# Main.net
KiCad netlist of a schematic drawn in EAGLE
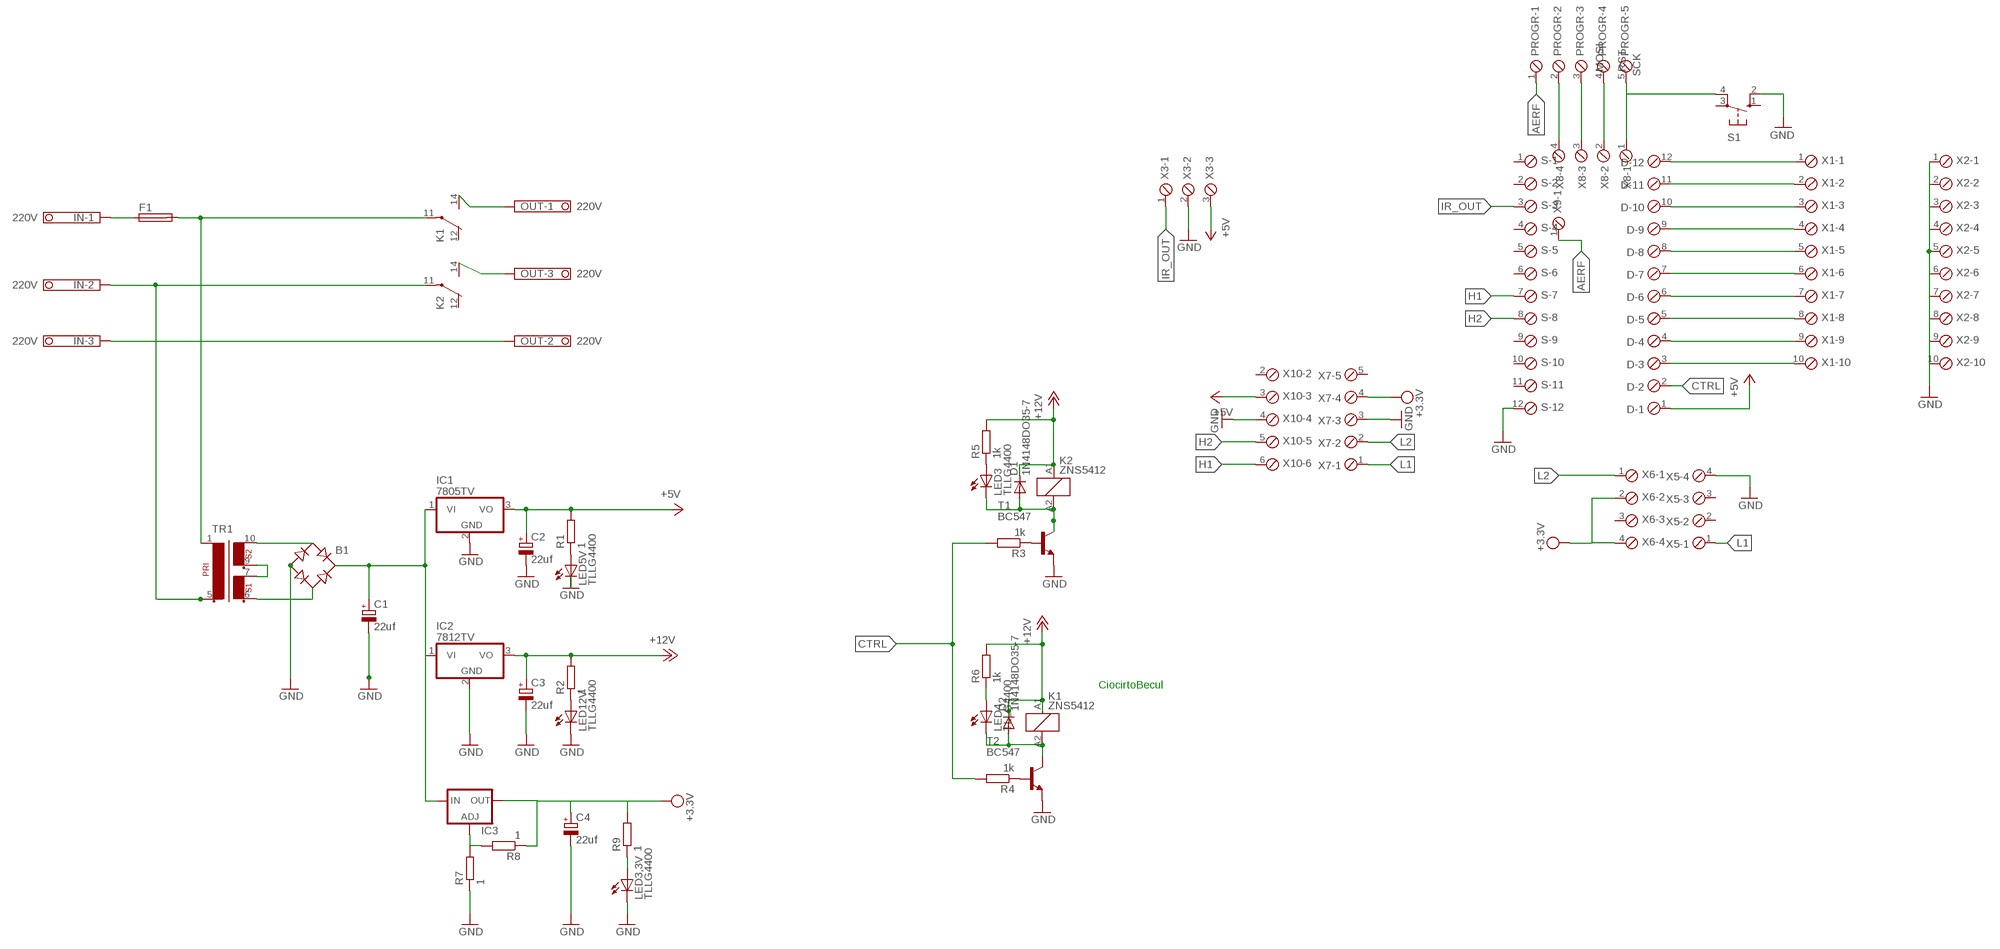
[diagram p0: schematic, sheet 1]

(export (version "E")
  (design (tool "Eeschema 10.0.6"))
  (components
    (comp (ref "B1")
      (value "RB1A")
      (footprint "eagle-import:RB1A")
      (libsource (lib "eagle-import") (part "RB1A"))
    )
    (comp (ref "C1")
      (value "22uf")
      (footprint "eagle-import:E2-4")
      (libsource (lib "eagle-import") (part "CPOL-EUE2-4"))
    )
    (comp (ref "C2")
      (value "22uf")
      (footprint "eagle-import:E2-4")
      (libsource (lib "eagle-import") (part "CPOL-EUE2-4"))
    )
    (comp (ref "C3")
      (value "22uf")
      (footprint "eagle-import:E2-4")
      (libsource (lib "eagle-import") (part "CPOL-EUE2-4"))
    )
    (comp (ref "C4")
      (value "22uf")
      (footprint "eagle-import:E2-4")
      (libsource (lib "eagle-import") (part "CPOL-EUE2-4"))
    )
    (comp (ref "D")
      (value "MPT12")
      (footprint "eagle-import:12POL254")
      (libsource (lib "eagle-import") (part "MPT12"))
    )
    (comp (ref "D1")
      (value "1N4148DO35-7")
      (footprint "eagle-import:DO35-7")
      (libsource (lib "eagle-import") (part "1N4148DO35-7"))
    )
    (comp (ref "D2")
      (value "1N4148DO35-7")
      (footprint "eagle-import:DO35-7")
      (libsource (lib "eagle-import") (part "1N4148DO35-7"))
    )
    (comp (ref "F1")
      (value "SH25")
      (footprint "eagle-import:SH25")
      (fields (field (name "MF") "SCHURTER") (field (name "MPN") "0031.8211"))
      (libsource (lib "eagle-import") (part "SH25"))
    )
    (comp (ref "IC1")
      (value "7805TV")
      (footprint "eagle-import:TO220V")
      (libsource (lib "eagle-import") (part "78TV05"))
    )
    (comp (ref "IC2")
      (value "7812TV")
      (footprint "eagle-import:TO220V")
      (libsource (lib "eagle-import") (part "78TV12"))
    )
    (comp (ref "IC3")
      (value "LM317TS")
      (footprint "eagle-import:317TS")
      (libsource (lib "eagle-import") (part "LM317TS"))
    )
    (comp (ref "IN")
      (value "220V")
      (footprint "eagle-import:1751251")
      (libsource (lib "eagle-import") (part "1751251"))
    )
    (comp (ref "K1")
      (value "ZNS5412")
      (footprint "eagle-import:ZN5")
      (libsource (lib "eagle-import") (part "ZNS5412"))
    )
    (comp (ref "K2")
      (value "ZNS5412")
      (footprint "eagle-import:ZN5")
      (libsource (lib "eagle-import") (part "ZNS5412"))
    )
    (comp (ref "LED3")
      (value "TLLG4400")
      (footprint "eagle-import:LED3MM")
      (fields (field (name "MF") "VISHAY SEMICONDUCTOR"))
      (libsource (lib "eagle-import") (part "TLLG4400"))
    )
    (comp (ref "LED3,3V")
      (value "TLLG4400")
      (footprint "eagle-import:LED3MM")
      (fields (field (name "MF") "VISHAY SEMICONDUCTOR"))
      (libsource (lib "eagle-import") (part "TLLG4400"))
    )
    (comp (ref "LED4")
      (value "TLLG4400")
      (footprint "eagle-import:LED3MM")
      (fields (field (name "MF") "VISHAY SEMICONDUCTOR"))
      (libsource (lib "eagle-import") (part "TLLG4400"))
    )
    (comp (ref "LED5V")
      (value "TLLG4400")
      (footprint "eagle-import:LED3MM")
      (fields (field (name "MF") "VISHAY SEMICONDUCTOR"))
      (libsource (lib "eagle-import") (part "TLLG4400"))
    )
    (comp (ref "LED12V")
      (value "TLLG4400")
      (footprint "eagle-import:LED3MM")
      (fields (field (name "MF") "VISHAY SEMICONDUCTOR"))
      (libsource (lib "eagle-import") (part "TLLG4400"))
    )
    (comp (ref "OUT")
      (value "220V")
      (footprint "eagle-import:1751251")
      (libsource (lib "eagle-import") (part "1751251"))
    )
    (comp (ref "PROGR")
      (value "SCK")
      (footprint "eagle-import:5POL254")
      (fields (field (name "KIND") "RST") (field (name "KIND2") "MOSI"))
      (libsource (lib "eagle-import") (part "MPT5"))
    )
    (comp (ref "R1")
      (value "1")
      (footprint "eagle-import:0204_5")
      (libsource (lib "eagle-import") (part "R-EU_0204/5"))
    )
    (comp (ref "R2")
      (value "1")
      (footprint "eagle-import:0204_5")
      (libsource (lib "eagle-import") (part "R-EU_0204/5"))
    )
    (comp (ref "R3")
      (value "1k")
      (footprint "eagle-import:0204_5")
      (libsource (lib "eagle-import") (part "R-EU_0204/5"))
    )
    (comp (ref "R4")
      (value "1k")
      (footprint "eagle-import:0204_5")
      (libsource (lib "eagle-import") (part "R-EU_0204/5"))
    )
    (comp (ref "R5")
      (value "1k")
      (footprint "eagle-import:0204_5")
      (libsource (lib "eagle-import") (part "R-EU_0204/5"))
    )
    (comp (ref "R6")
      (value "1k")
      (footprint "eagle-import:0204_5")
      (libsource (lib "eagle-import") (part "R-EU_0204/5"))
    )
    (comp (ref "R7")
      (value "1")
      (footprint "eagle-import:0204_5")
      (libsource (lib "eagle-import") (part "R-EU_0204/5"))
    )
    (comp (ref "R8")
      (value "1")
      (footprint "eagle-import:0204_5")
      (libsource (lib "eagle-import") (part "R-EU_0204/5"))
    )
    (comp (ref "R9")
      (value "1")
      (footprint "eagle-import:0204_5")
      (libsource (lib "eagle-import") (part "R-EU_0204/5"))
    )
    (comp (ref "S")
      (value "MPT12")
      (footprint "eagle-import:12POL254")
      (libsource (lib "eagle-import") (part "MPT12"))
    )
    (comp (ref "S1")
      (value "10-XX")
      (footprint "eagle-import:B3F-10XX")
      (fields (field (name "MPN") "B3F-1000"))
      (libsource (lib "eagle-import") (part "10-XX"))
    )
    (comp (ref "T1")
      (value "BC547")
      (footprint "eagle-import:TO92")
      (libsource (lib "eagle-import") (part "BC547"))
    )
    (comp (ref "T2")
      (value "BC547")
      (footprint "eagle-import:TO92")
      (libsource (lib "eagle-import") (part "BC547"))
    )
    (comp (ref "TR1")
      (value "EI30-2")
      (footprint "eagle-import:EI30-2")
      (libsource (lib "eagle-import") (part "EI30-2"))
    )
    (comp (ref "X1")
      (value "MPT10")
      (footprint "eagle-import:10POL254")
      (libsource (lib "eagle-import") (part "MPT10"))
    )
    (comp (ref "X2")
      (value "MPT10")
      (footprint "eagle-import:10POL254")
      (libsource (lib "eagle-import") (part "MPT10"))
    )
    (comp (ref "X3")
      (value "MPT3")
      (footprint "eagle-import:3POL254")
      (libsource (lib "eagle-import") (part "MPT3"))
    )
    (comp (ref "X5")
      (value "MPT4")
      (footprint "eagle-import:4POL254")
      (libsource (lib "eagle-import") (part "MPT4"))
    )
    (comp (ref "X6")
      (value "MPT4")
      (footprint "eagle-import:4POL254")
      (libsource (lib "eagle-import") (part "MPT4"))
    )
    (comp (ref "X7")
      (value "MPT6")
      (footprint "eagle-import:6POL254")
      (libsource (lib "eagle-import") (part "MPT6"))
    )
    (comp (ref "X8")
      (value "MPT4")
      (footprint "eagle-import:4POL254")
      (libsource (lib "eagle-import") (part "MPT4"))
    )
    (comp (ref "X9")
      (value "MPT2")
      (footprint "eagle-import:2POL254")
      (libsource (lib "eagle-import") (part "MPT2"))
    )
    (comp (ref "X10")
      (value "MPT6")
      (footprint "eagle-import:6POL254")
      (libsource (lib "eagle-import") (part "MPT6"))
    )
  )
  (nets
    (net (code "1") (name "+3.3V") (class "Default")
      (node (ref "C4") (pin "+") (pinfunction "+_+") (pintype "passive"))
      (node (ref "IC3") (pin "2") (pinfunction "OUT_2") (pintype "passive"))
      (node (ref "R8") (pin "1") (pinfunction "1_1") (pintype "passive"))
      (node (ref "R9") (pin "2") (pinfunction "2_2") (pintype "passive"))
      (node (ref "X6") (pin "2") (pinfunction "1_2") (pintype "passive"))
      (node (ref "X6") (pin "4") (pinfunction "1_4") (pintype "passive"))
      (node (ref "X7") (pin "4") (pinfunction "1_4") (pintype "passive"))
    )
    (net (code "2") (name "+5V") (class "Default")
      (node (ref "C2") (pin "+") (pinfunction "+_+") (pintype "passive"))
      (node (ref "D") (pin "1") (pinfunction "1_1") (pintype "passive"))
      (node (ref "IC1") (pin "3") (pinfunction "VO_3") (pintype "passive"))
      (node (ref "R1") (pin "2") (pinfunction "2_2") (pintype "passive"))
      (node (ref "X10") (pin "3") (pinfunction "1_3") (pintype "passive"))
      (node (ref "X3") (pin "3") (pinfunction "1_3") (pintype "passive"))
    )
    (net (code "3") (name "+12V") (class "Default")
      (node (ref "C3") (pin "+") (pinfunction "+_+") (pintype "passive"))
      (node (ref "D1") (pin "C") (pinfunction "C_C") (pintype "passive"))
      (node (ref "D2") (pin "C") (pinfunction "C_C") (pintype "passive"))
      (node (ref "IC2") (pin "3") (pinfunction "VO_3") (pintype "passive"))
      (node (ref "K1") (pin "A1") (pinfunction "1_A1") (pintype "passive"))
      (node (ref "K2") (pin "A1") (pinfunction "1_A1") (pintype "passive"))
      (node (ref "R2") (pin "2") (pinfunction "2_2") (pintype "passive"))
      (node (ref "R5") (pin "2") (pinfunction "2_2") (pintype "passive"))
      (node (ref "R6") (pin "2") (pinfunction "2_2") (pintype "passive"))
    )
    (net (code "4") (name "AERF") (class "Default")
      (node (ref "PROGR") (pin "1") (pinfunction "1_1") (pintype "passive"))
      (node (ref "X9") (pin "1") (pinfunction "1_1") (pintype "passive"))
    )
    (net (code "5") (name "CTRL") (class "Default")
      (node (ref "D") (pin "2") (pinfunction "1_2") (pintype "passive"))
      (node (ref "R3") (pin "2") (pinfunction "2_2") (pintype "passive"))
      (node (ref "R4") (pin "2") (pinfunction "2_2") (pintype "passive"))
    )
    (net (code "6") (name "GND") (class "Default")
      (node (ref "B1") (pin "-") (pinfunction "-_-") (pintype "passive"))
      (node (ref "C1") (pin "-") (pinfunction "-_-") (pintype "passive"))
      (node (ref "C2") (pin "-") (pinfunction "-_-") (pintype "passive"))
      (node (ref "C3") (pin "-") (pinfunction "-_-") (pintype "passive"))
      (node (ref "C4") (pin "-") (pinfunction "-_-") (pintype "passive"))
      (node (ref "IC1") (pin "2") (pinfunction "GND_2") (pintype "passive"))
      (node (ref "IC2") (pin "2") (pinfunction "GND_2") (pintype "passive"))
      (node (ref "LED12V") (pin "K") (pinfunction "C_K") (pintype "passive"))
      (node (ref "LED3,3V") (pin "K") (pinfunction "C_K") (pintype "passive"))
      (node (ref "LED5V") (pin "K") (pinfunction "C_K") (pintype "passive"))
      (node (ref "R7") (pin "1") (pinfunction "1_1") (pintype "passive"))
      (node (ref "S") (pin "12") (pinfunction "1_12") (pintype "passive"))
      (node (ref "S1") (pin "2") (pinfunction "S1_2") (pintype "passive"))
      (node (ref "T1") (pin "1") (pinfunction "E_1") (pintype "passive"))
      (node (ref "T2") (pin "1") (pinfunction "E_1") (pintype "passive"))
      (node (ref "X10") (pin "4") (pinfunction "1_4") (pintype "passive"))
      (node (ref "X2") (pin "1") (pinfunction "1_1") (pintype "passive"))
      (node (ref "X2") (pin "10") (pinfunction "1_10") (pintype "passive"))
      (node (ref "X2") (pin "2") (pinfunction "1_2") (pintype "passive"))
      (node (ref "X2") (pin "3") (pinfunction "1_3") (pintype "passive"))
      (node (ref "X2") (pin "4") (pinfunction "1_4") (pintype "passive"))
      (node (ref "X2") (pin "5") (pinfunction "1_5") (pintype "passive"))
      (node (ref "X2") (pin "6") (pinfunction "1_6") (pintype "passive"))
      (node (ref "X2") (pin "7") (pinfunction "1_7") (pintype "passive"))
      (node (ref "X2") (pin "8") (pinfunction "1_8") (pintype "passive"))
      (node (ref "X2") (pin "9") (pinfunction "1_9") (pintype "passive"))
      (node (ref "X3") (pin "2") (pinfunction "1_2") (pintype "passive"))
      (node (ref "X5") (pin "4") (pinfunction "1_4") (pintype "passive"))
      (node (ref "X7") (pin "3") (pinfunction "1_3") (pintype "passive"))
    )
    (net (code "7") (name "H1") (class "Default")
      (node (ref "S") (pin "7") (pinfunction "1_7") (pintype "passive"))
      (node (ref "X10") (pin "6") (pinfunction "1_6") (pintype "passive"))
    )
    (net (code "8") (name "H2") (class "Default")
      (node (ref "S") (pin "8") (pinfunction "1_8") (pintype "passive"))
      (node (ref "X10") (pin "5") (pinfunction "1_5") (pintype "passive"))
    )
    (net (code "9") (name "IR_OUT") (class "Default")
      (node (ref "S") (pin "3") (pinfunction "1_3") (pintype "passive"))
      (node (ref "X3") (pin "1") (pinfunction "1_1") (pintype "passive"))
    )
    (net (code "10") (name "L1") (class "Default")
      (node (ref "X5") (pin "1") (pinfunction "1_1") (pintype "passive"))
      (node (ref "X7") (pin "1") (pinfunction "1_1") (pintype "passive"))
    )
    (net (code "11") (name "L2") (class "Default")
      (node (ref "X6") (pin "1") (pinfunction "1_1") (pintype "passive"))
      (node (ref "X7") (pin "2") (pinfunction "1_2") (pintype "passive"))
    )
    (net (code "12") (name "Net-(DB-1)") (class "Default")
      (node (ref "D") (pin "10") (pinfunction "1_10") (pintype "passive"))
      (node (ref "X1") (pin "3") (pinfunction "1_3") (pintype "passive"))
    )
    (net (code "13") (name "Net-(DC-1)") (class "Default")
      (node (ref "D") (pin "11") (pinfunction "1_11") (pintype "passive"))
      (node (ref "X1") (pin "2") (pinfunction "1_2") (pintype "passive"))
    )
    (net (code "14") (name "Net-(DD-1)") (class "Default")
      (node (ref "D") (pin "12") (pinfunction "1_12") (pintype "passive"))
      (node (ref "X1") (pin "1") (pinfunction "1_1") (pintype "passive"))
    )
    (net (code "15") (name "Net-(DF-1)") (class "Default")
      (node (ref "D") (pin "3") (pinfunction "1_3") (pintype "passive"))
      (node (ref "X1") (pin "10") (pinfunction "1_10") (pintype "passive"))
    )
    (net (code "16") (name "Net-(DG-1)") (class "Default")
      (node (ref "D") (pin "4") (pinfunction "1_4") (pintype "passive"))
      (node (ref "X1") (pin "9") (pinfunction "1_9") (pintype "passive"))
    )
    (net (code "17") (name "Net-(DH-1)") (class "Default")
      (node (ref "D") (pin "5") (pinfunction "1_5") (pintype "passive"))
      (node (ref "X1") (pin "8") (pinfunction "1_8") (pintype "passive"))
    )
    (net (code "18") (name "Net-(DI-1)") (class "Default")
      (node (ref "D") (pin "6") (pinfunction "1_6") (pintype "passive"))
      (node (ref "X1") (pin "7") (pinfunction "1_7") (pintype "passive"))
    )
    (net (code "19") (name "Net-(DJ-1)") (class "Default")
      (node (ref "D") (pin "7") (pinfunction "1_7") (pintype "passive"))
      (node (ref "X1") (pin "6") (pinfunction "1_6") (pintype "passive"))
    )
    (net (code "20") (name "Net-(DK-1)") (class "Default")
      (node (ref "D") (pin "8") (pinfunction "1_8") (pintype "passive"))
      (node (ref "X1") (pin "5") (pinfunction "1_5") (pintype "passive"))
    )
    (net (code "21") (name "Net-(DL-1)") (class "Default")
      (node (ref "D") (pin "9") (pinfunction "1_9") (pintype "passive"))
      (node (ref "X1") (pin "4") (pinfunction "1_4") (pintype "passive"))
    )
    (net (code "22") (name "Net-(IC1-VI)") (class "Default")
      (node (ref "B1") (pin "+") (pinfunction "+_+") (pintype "passive"))
      (node (ref "C1") (pin "+") (pinfunction "+_+") (pintype "passive"))
      (node (ref "IC1") (pin "1") (pinfunction "VI_1") (pintype "input"))
      (node (ref "IC2") (pin "1") (pinfunction "VI_1") (pintype "input"))
      (node (ref "IC3") (pin "3") (pinfunction "IN_3") (pintype "input"))
    )
    (net (code "23") (name "Net-(IC3-ADJ)") (class "Default")
      (node (ref "IC3") (pin "1") (pinfunction "ADJ_1") (pintype "input"))
      (node (ref "R7") (pin "2") (pinfunction "2_2") (pintype "passive"))
      (node (ref "R8") (pin "2") (pinfunction "2_2") (pintype "passive"))
    )
    (net (code "24") (name "Net-(INA-K)") (class "Default")
      (node (ref "F1") (pin "1") (pinfunction "1_1") (pintype "passive"))
      (node (ref "IN") (pin "1") (pinfunction "K_1") (pintype "passive"))
    )
    (net (code "25") (name "Net-(INB-K)") (class "Default")
      (node (ref "IN") (pin "2") (pinfunction "K_2") (pintype "passive"))
      (node (ref "K2") (pin "11") (pinfunction "P_11") (pintype "passive"))
      (node (ref "TR1") (pin "5") (pinfunction "2_5") (pintype "passive"))
    )
    (net (code "26") (name "Net-(INC-K)") (class "Default")
      (node (ref "IN") (pin "3") (pinfunction "K_3") (pintype "passive"))
      (node (ref "OUT") (pin "2") (pinfunction "K_2") (pintype "passive"))
    )
    (net (code "27") (name "Net-(K1A-2)") (class "Default")
      (node (ref "D2") (pin "A") (pinfunction "A_A") (pintype "passive"))
      (node (ref "K1") (pin "A2") (pinfunction "2_A2") (pintype "passive"))
      (node (ref "LED4") (pin "K") (pinfunction "C_K") (pintype "passive"))
      (node (ref "T2") (pin "3") (pinfunction "C_3") (pintype "passive"))
    )
    (net (code "28") (name "Net-(K1B-P)") (class "Default")
      (node (ref "F1") (pin "2") (pinfunction "2_2") (pintype "passive"))
      (node (ref "K1") (pin "11") (pinfunction "P_11") (pintype "passive"))
      (node (ref "TR1") (pin "1") (pinfunction "1_1") (pintype "passive"))
    )
    (net (code "29") (name "Net-(K1B-S)") (class "Default")
      (node (ref "K1") (pin "14") (pinfunction "S_14") (pintype "passive"))
      (node (ref "OUT") (pin "1") (pinfunction "K_1") (pintype "passive"))
    )
    (net (code "30") (name "Net-(K2A-2)") (class "Default")
      (node (ref "D1") (pin "A") (pinfunction "A_A") (pintype "passive"))
      (node (ref "K2") (pin "A2") (pinfunction "2_A2") (pintype "passive"))
      (node (ref "LED3") (pin "K") (pinfunction "C_K") (pintype "passive"))
      (node (ref "T1") (pin "3") (pinfunction "C_3") (pintype "passive"))
    )
    (net (code "31") (name "Net-(K2B-S)") (class "Default")
      (node (ref "K2") (pin "14") (pinfunction "S_14") (pintype "passive"))
      (node (ref "OUT") (pin "3") (pinfunction "K_3") (pintype "passive"))
    )
    (net (code "32") (name "Net-(LED3,3V-PadA)") (class "Default")
      (node (ref "LED3,3V") (pin "A") (pinfunction "A_A") (pintype "passive"))
      (node (ref "R9") (pin "1") (pinfunction "1_1") (pintype "passive"))
    )
    (net (code "33") (name "Net-(LED3-PadA)") (class "Default")
      (node (ref "LED3") (pin "A") (pinfunction "A_A") (pintype "passive"))
      (node (ref "R5") (pin "1") (pinfunction "1_1") (pintype "passive"))
    )
    (net (code "34") (name "Net-(LED4-PadA)") (class "Default")
      (node (ref "LED4") (pin "A") (pinfunction "A_A") (pintype "passive"))
      (node (ref "R6") (pin "1") (pinfunction "1_1") (pintype "passive"))
    )
    (net (code "35") (name "Net-(LED5V-PadA)") (class "Default")
      (node (ref "LED5V") (pin "A") (pinfunction "A_A") (pintype "passive"))
      (node (ref "R1") (pin "1") (pinfunction "1_1") (pintype "passive"))
    )
    (net (code "36") (name "Net-(LED12V-PadA)") (class "Default")
      (node (ref "LED12V") (pin "A") (pinfunction "A_A") (pintype "passive"))
      (node (ref "R2") (pin "1") (pinfunction "1_1") (pintype "passive"))
    )
    (net (code "37") (name "Net-(PROGRB-1)") (class "Default")
      (node (ref "PROGR") (pin "2") (pinfunction "1_2") (pintype "passive"))
      (node (ref "X8") (pin "4") (pinfunction "1_4") (pintype "passive"))
    )
    (net (code "38") (name "Net-(PROGRC-1)") (class "Default")
      (node (ref "PROGR") (pin "3") (pinfunction "1_3") (pintype "passive"))
      (node (ref "X8") (pin "3") (pinfunction "1_3") (pintype "passive"))
    )
    (net (code "39") (name "Net-(PROGRD-1)") (class "Default")
      (node (ref "PROGR") (pin "4") (pinfunction "1_4") (pintype "passive"))
      (node (ref "X8") (pin "2") (pinfunction "1_2") (pintype "passive"))
    )
    (net (code "40") (name "Net-(PROGRE-1)") (class "Default")
      (node (ref "PROGR") (pin "5") (pinfunction "1_5") (pintype "passive"))
      (node (ref "S1") (pin "4") (pinfunction "P1_4") (pintype "passive"))
      (node (ref "X8") (pin "1") (pinfunction "1_1") (pintype "passive"))
    )
    (net (code "41") (name "Net-(T1-B)") (class "Default")
      (node (ref "R3") (pin "1") (pinfunction "1_1") (pintype "passive"))
      (node (ref "T1") (pin "2") (pinfunction "B_2") (pintype "passive"))
    )
    (net (code "42") (name "Net-(T2-B)") (class "Default")
      (node (ref "R4") (pin "1") (pinfunction "1_1") (pintype "passive"))
      (node (ref "T2") (pin "2") (pinfunction "B_2") (pintype "passive"))
    )
    (net (code "43") (name "Net-(TR1-3)") (class "Default")
      (node (ref "B1") (pin "AC2") (pinfunction "AC2_AC2") (pintype "passive"))
      (node (ref "TR1") (pin "6") (pinfunction "3_6") (pintype "passive"))
    )
    (net (code "44") (name "Net-(TR1-4)") (class "Default")
      (node (ref "TR1") (pin "7") (pinfunction "4_7") (pintype "passive"))
      (node (ref "TR1") (pin "9") (pinfunction "5_9") (pintype "passive"))
    )
    (net (code "45") (name "Net-(TR1-6)") (class "Default")
      (node (ref "B1") (pin "AC1") (pinfunction "AC1_AC1") (pintype "passive"))
      (node (ref "TR1") (pin "10") (pinfunction "6_10") (pintype "passive"))
    )
    (net (code "46") (name "unconnected-(K1B-O-Pad12)") (class "Default")
      (node (ref "K1") (pin "12") (pinfunction "O_12") (pintype "passive"))
    )
    (net (code "47") (name "unconnected-(K2B-O-Pad12)") (class "Default")
      (node (ref "K2") (pin "12") (pinfunction "O_12") (pintype "passive"))
    )
    (net (code "48") (name "unconnected-(S-Pad1)") (class "Default")
      (node (ref "S") (pin "1") (pinfunction "1_1") (pintype "passive"))
    )
    (net (code "49") (name "unconnected-(S1-P-Pad3)") (class "Default")
      (node (ref "S1") (pin "3") (pinfunction "P_3") (pintype "passive"))
    )
    (net (code "50") (name "unconnected-(S1-S-Pad1)") (class "Default")
      (node (ref "S1") (pin "1") (pinfunction "S_1") (pintype "passive"))
    )
    (net (code "51") (name "unconnected-(SB-1-Pad10)") (class "Default")
      (node (ref "S") (pin "10") (pinfunction "1_10") (pintype "passive"))
    )
    (net (code "52") (name "unconnected-(SC-1-Pad11)") (class "Default")
      (node (ref "S") (pin "11") (pinfunction "1_11") (pintype "passive"))
    )
    (net (code "53") (name "unconnected-(SE-1-Pad2)") (class "Default")
      (node (ref "S") (pin "2") (pinfunction "1_2") (pintype "passive"))
    )
    (net (code "54") (name "unconnected-(SG-1-Pad4)") (class "Default")
      (node (ref "S") (pin "4") (pinfunction "1_4") (pintype "passive"))
    )
    (net (code "55") (name "unconnected-(SH-1-Pad5)") (class "Default")
      (node (ref "S") (pin "5") (pinfunction "1_5") (pintype "passive"))
    )
    (net (code "56") (name "unconnected-(SI-1-Pad6)") (class "Default")
      (node (ref "S") (pin "6") (pinfunction "1_6") (pintype "passive"))
    )
    (net (code "57") (name "unconnected-(SL-1-Pad9)") (class "Default")
      (node (ref "S") (pin "9") (pinfunction "1_9") (pintype "passive"))
    )
    (net (code "58") (name "unconnected-(X5B-1-Pad2)") (class "Default")
      (node (ref "X5") (pin "2") (pinfunction "1_2") (pintype "passive"))
    )
    (net (code "59") (name "unconnected-(X5C-1-Pad3)") (class "Default")
      (node (ref "X5") (pin "3") (pinfunction "1_3") (pintype "passive"))
    )
    (net (code "60") (name "unconnected-(X6C-1-Pad3)") (class "Default")
      (node (ref "X6") (pin "3") (pinfunction "1_3") (pintype "passive"))
    )
    (net (code "61") (name "unconnected-(X7E-1-Pad5)") (class "Default")
      (node (ref "X7") (pin "5") (pinfunction "1_5") (pintype "passive"))
    )
    (net (code "62") (name "unconnected-(X10B-1-Pad2)") (class "Default")
      (node (ref "X10") (pin "2") (pinfunction "1_2") (pintype "passive"))
    )
  )
)
